# AMS_Test_Board_rev1.net
KiCad netlist of a schematic drawn in EAGLE
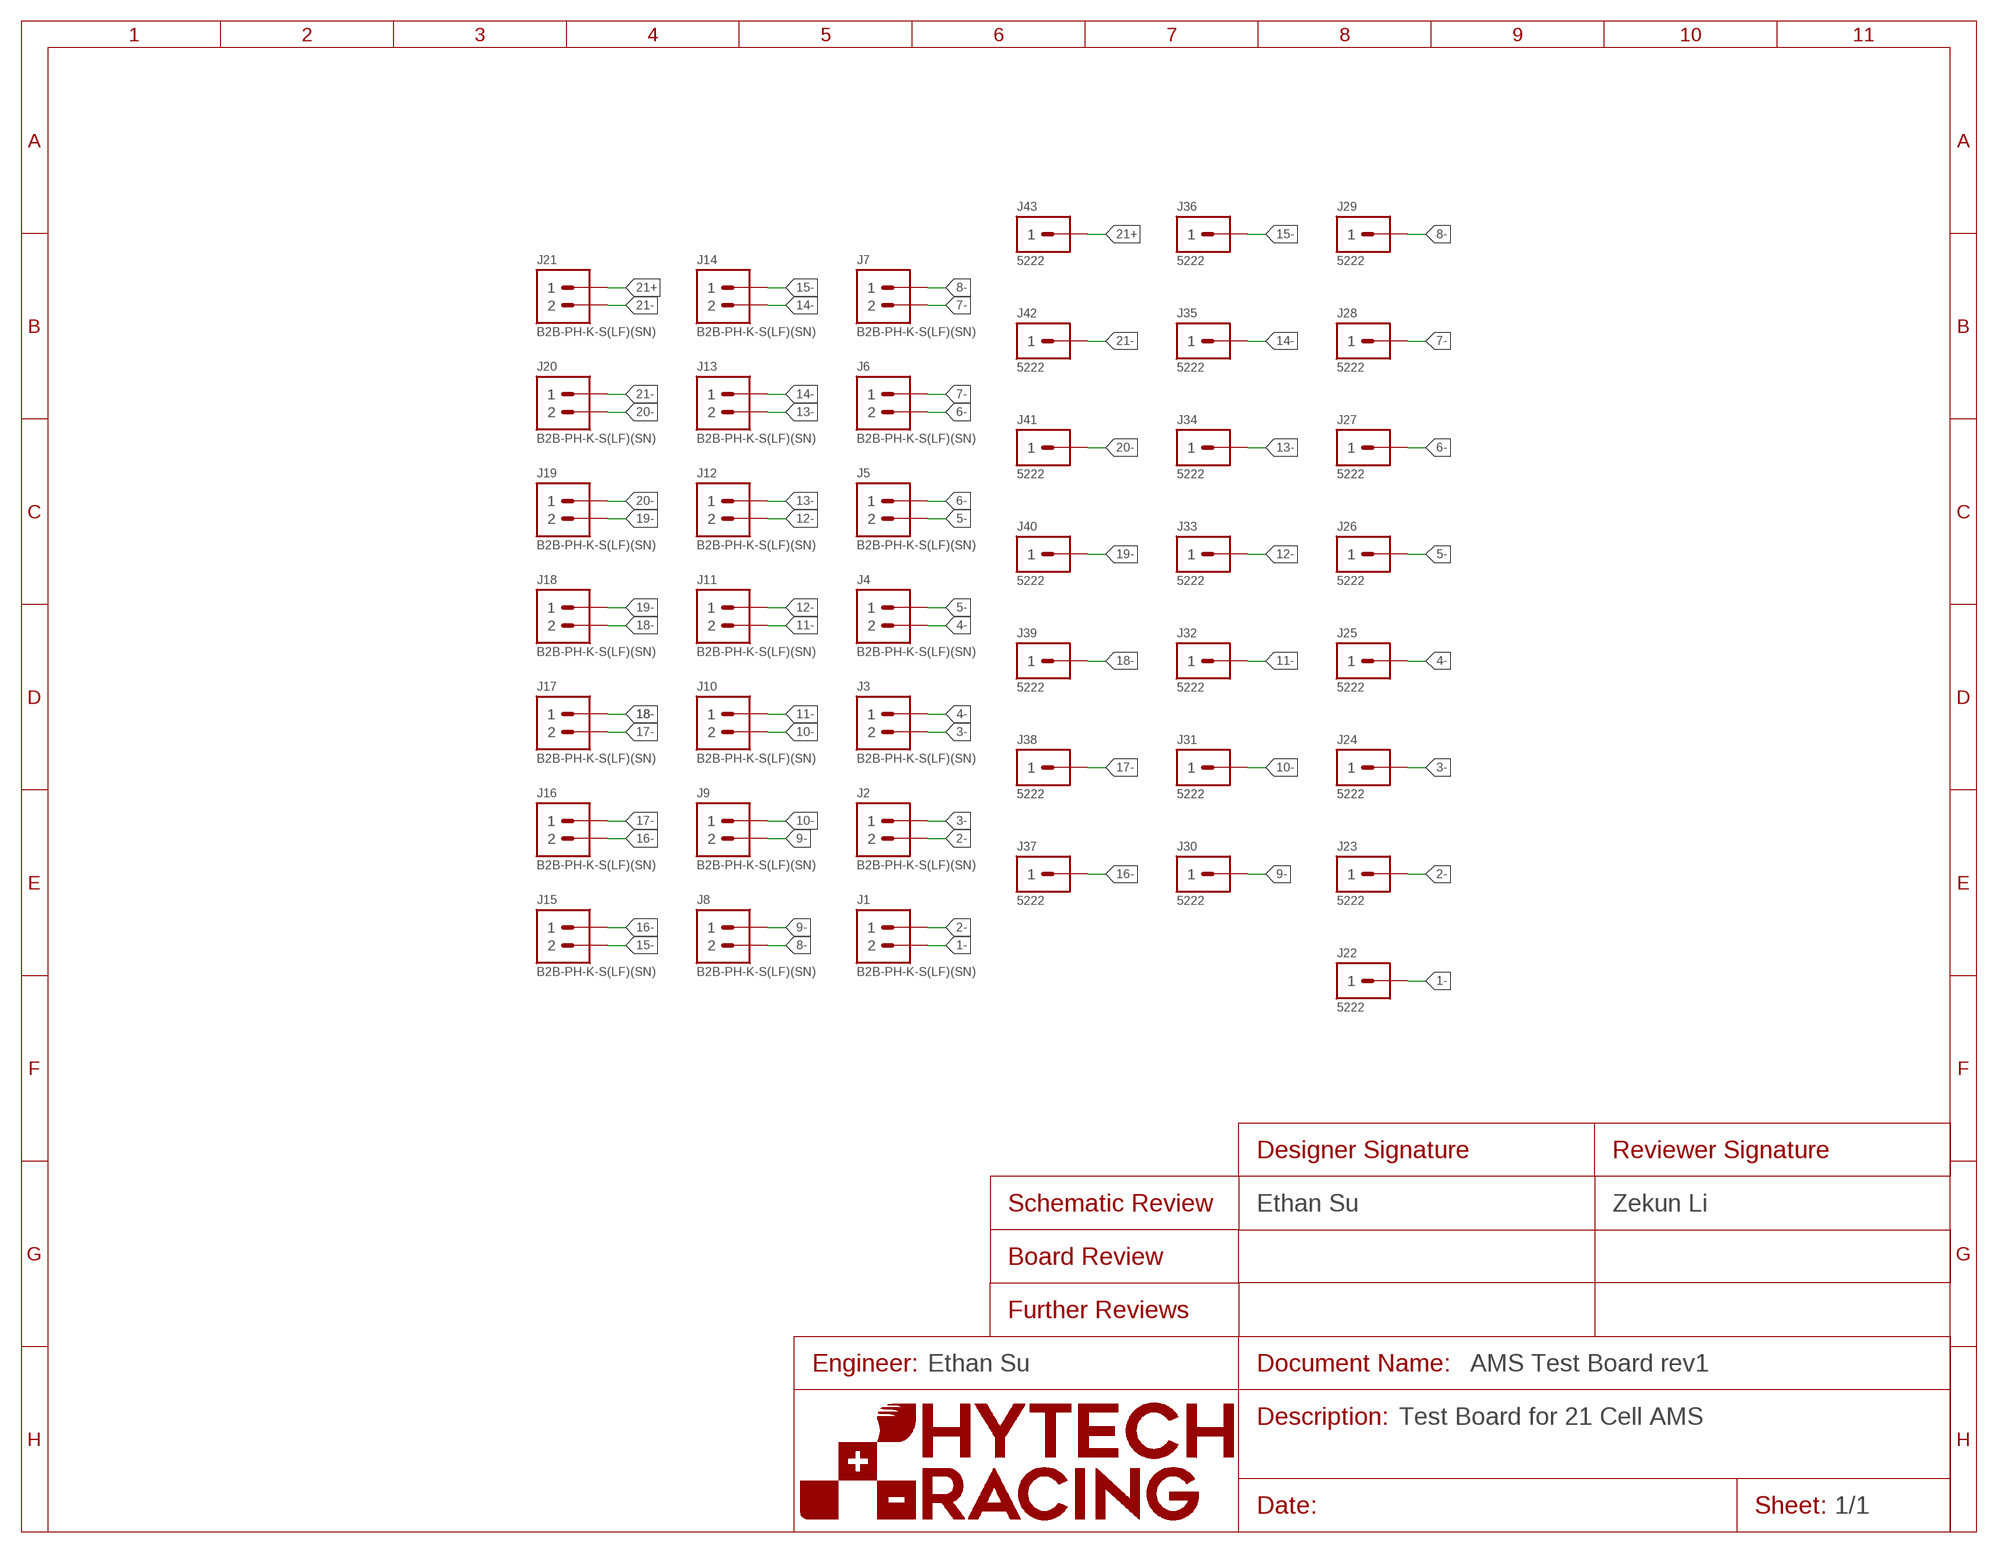
[diagram p0: schematic, sheet 1]

(export (version "E")
  (design (tool "Eeschema 10.0.6"))
  (components
    (comp (ref "J1")
      (value "CONNECTOR-2__B2B-PH-K")
      (footprint "eagle-import:B2B-PH-K")
      (fields
        (field (name "MANUFACTURER") "JST Sales America Inc.")
        (field (name "MPN") "B2B-PH-K-S(LF)(SN)")
      )
      (libsource (lib "eagle-import") (part "CONNECTOR-2_?_B2B-PH-K"))
    )
    (comp (ref "J2")
      (value "CONNECTOR-2__B2B-PH-K")
      (footprint "eagle-import:B2B-PH-K")
      (fields
        (field (name "MANUFACTURER") "JST Sales America Inc.")
        (field (name "MPN") "B2B-PH-K-S(LF)(SN)")
      )
      (libsource (lib "eagle-import") (part "CONNECTOR-2_?_B2B-PH-K"))
    )
    (comp (ref "J3")
      (value "CONNECTOR-2__B2B-PH-K")
      (footprint "eagle-import:B2B-PH-K")
      (fields
        (field (name "MANUFACTURER") "JST Sales America Inc.")
        (field (name "MPN") "B2B-PH-K-S(LF)(SN)")
      )
      (libsource (lib "eagle-import") (part "CONNECTOR-2_?_B2B-PH-K"))
    )
    (comp (ref "J4")
      (value "CONNECTOR-2__B2B-PH-K")
      (footprint "eagle-import:B2B-PH-K")
      (fields
        (field (name "MANUFACTURER") "JST Sales America Inc.")
        (field (name "MPN") "B2B-PH-K-S(LF)(SN)")
      )
      (libsource (lib "eagle-import") (part "CONNECTOR-2_?_B2B-PH-K"))
    )
    (comp (ref "J5")
      (value "CONNECTOR-2__B2B-PH-K")
      (footprint "eagle-import:B2B-PH-K")
      (fields
        (field (name "MANUFACTURER") "JST Sales America Inc.")
        (field (name "MPN") "B2B-PH-K-S(LF)(SN)")
      )
      (libsource (lib "eagle-import") (part "CONNECTOR-2_?_B2B-PH-K"))
    )
    (comp (ref "J6")
      (value "CONNECTOR-2__B2B-PH-K")
      (footprint "eagle-import:B2B-PH-K")
      (fields
        (field (name "MANUFACTURER") "JST Sales America Inc.")
        (field (name "MPN") "B2B-PH-K-S(LF)(SN)")
      )
      (libsource (lib "eagle-import") (part "CONNECTOR-2_?_B2B-PH-K"))
    )
    (comp (ref "J7")
      (value "CONNECTOR-2__B2B-PH-K")
      (footprint "eagle-import:B2B-PH-K")
      (fields
        (field (name "MANUFACTURER") "JST Sales America Inc.")
        (field (name "MPN") "B2B-PH-K-S(LF)(SN)")
      )
      (libsource (lib "eagle-import") (part "CONNECTOR-2_?_B2B-PH-K"))
    )
    (comp (ref "J8")
      (value "CONNECTOR-2__B2B-PH-K")
      (footprint "eagle-import:B2B-PH-K")
      (fields
        (field (name "MANUFACTURER") "JST Sales America Inc.")
        (field (name "MPN") "B2B-PH-K-S(LF)(SN)")
      )
      (libsource (lib "eagle-import") (part "CONNECTOR-2_?_B2B-PH-K"))
    )
    (comp (ref "J9")
      (value "CONNECTOR-2__B2B-PH-K")
      (footprint "eagle-import:B2B-PH-K")
      (fields
        (field (name "MANUFACTURER") "JST Sales America Inc.")
        (field (name "MPN") "B2B-PH-K-S(LF)(SN)")
      )
      (libsource (lib "eagle-import") (part "CONNECTOR-2_?_B2B-PH-K"))
    )
    (comp (ref "J10")
      (value "CONNECTOR-2__B2B-PH-K")
      (footprint "eagle-import:B2B-PH-K")
      (fields
        (field (name "MANUFACTURER") "JST Sales America Inc.")
        (field (name "MPN") "B2B-PH-K-S(LF)(SN)")
      )
      (libsource (lib "eagle-import") (part "CONNECTOR-2_?_B2B-PH-K"))
    )
    (comp (ref "J11")
      (value "CONNECTOR-2__B2B-PH-K")
      (footprint "eagle-import:B2B-PH-K")
      (fields
        (field (name "MANUFACTURER") "JST Sales America Inc.")
        (field (name "MPN") "B2B-PH-K-S(LF)(SN)")
      )
      (libsource (lib "eagle-import") (part "CONNECTOR-2_?_B2B-PH-K"))
    )
    (comp (ref "J12")
      (value "CONNECTOR-2__B2B-PH-K")
      (footprint "eagle-import:B2B-PH-K")
      (fields
        (field (name "MANUFACTURER") "JST Sales America Inc.")
        (field (name "MPN") "B2B-PH-K-S(LF)(SN)")
      )
      (libsource (lib "eagle-import") (part "CONNECTOR-2_?_B2B-PH-K"))
    )
    (comp (ref "J13")
      (value "CONNECTOR-2__B2B-PH-K")
      (footprint "eagle-import:B2B-PH-K")
      (fields
        (field (name "MANUFACTURER") "JST Sales America Inc.")
        (field (name "MPN") "B2B-PH-K-S(LF)(SN)")
      )
      (libsource (lib "eagle-import") (part "CONNECTOR-2_?_B2B-PH-K"))
    )
    (comp (ref "J14")
      (value "CONNECTOR-2__B2B-PH-K")
      (footprint "eagle-import:B2B-PH-K")
      (fields
        (field (name "MANUFACTURER") "JST Sales America Inc.")
        (field (name "MPN") "B2B-PH-K-S(LF)(SN)")
      )
      (libsource (lib "eagle-import") (part "CONNECTOR-2_?_B2B-PH-K"))
    )
    (comp (ref "J15")
      (value "CONNECTOR-2__B2B-PH-K")
      (footprint "eagle-import:B2B-PH-K")
      (fields
        (field (name "MANUFACTURER") "JST Sales America Inc.")
        (field (name "MPN") "B2B-PH-K-S(LF)(SN)")
      )
      (libsource (lib "eagle-import") (part "CONNECTOR-2_?_B2B-PH-K"))
    )
    (comp (ref "J16")
      (value "CONNECTOR-2__B2B-PH-K")
      (footprint "eagle-import:B2B-PH-K")
      (fields
        (field (name "MANUFACTURER") "JST Sales America Inc.")
        (field (name "MPN") "B2B-PH-K-S(LF)(SN)")
      )
      (libsource (lib "eagle-import") (part "CONNECTOR-2_?_B2B-PH-K"))
    )
    (comp (ref "J17")
      (value "CONNECTOR-2__B2B-PH-K")
      (footprint "eagle-import:B2B-PH-K")
      (fields
        (field (name "MANUFACTURER") "JST Sales America Inc.")
        (field (name "MPN") "B2B-PH-K-S(LF)(SN)")
      )
      (libsource (lib "eagle-import") (part "CONNECTOR-2_?_B2B-PH-K"))
    )
    (comp (ref "J18")
      (value "CONNECTOR-2__B2B-PH-K")
      (footprint "eagle-import:B2B-PH-K")
      (fields
        (field (name "MANUFACTURER") "JST Sales America Inc.")
        (field (name "MPN") "B2B-PH-K-S(LF)(SN)")
      )
      (libsource (lib "eagle-import") (part "CONNECTOR-2_?_B2B-PH-K"))
    )
    (comp (ref "J19")
      (value "CONNECTOR-2__B2B-PH-K")
      (footprint "eagle-import:B2B-PH-K")
      (fields
        (field (name "MANUFACTURER") "JST Sales America Inc.")
        (field (name "MPN") "B2B-PH-K-S(LF)(SN)")
      )
      (libsource (lib "eagle-import") (part "CONNECTOR-2_?_B2B-PH-K"))
    )
    (comp (ref "J20")
      (value "CONNECTOR-2__B2B-PH-K")
      (footprint "eagle-import:B2B-PH-K")
      (fields
        (field (name "MANUFACTURER") "JST Sales America Inc.")
        (field (name "MPN") "B2B-PH-K-S(LF)(SN)")
      )
      (libsource (lib "eagle-import") (part "CONNECTOR-2_?_B2B-PH-K"))
    )
    (comp (ref "J21")
      (value "CONNECTOR-2__B2B-PH-K")
      (footprint "eagle-import:B2B-PH-K")
      (fields
        (field (name "MANUFACTURER") "JST Sales America Inc.")
        (field (name "MPN") "B2B-PH-K-S(LF)(SN)")
      )
      (libsource (lib "eagle-import") (part "CONNECTOR-2_?_B2B-PH-K"))
    )
    (comp (ref "J22")
      (value "CONNECTOR-1_5222")
      (footprint "eagle-import:5222")
      (fields (field (name "MPN") "5222") (field (name "MANUFACTURER") "Keystone Electronics"))
      (libsource (lib "eagle-import") (part "CONNECTOR-1_?5222"))
    )
    (comp (ref "J23")
      (value "CONNECTOR-1_5222")
      (footprint "eagle-import:5222")
      (fields (field (name "MPN") "5222") (field (name "MANUFACTURER") "Keystone Electronics"))
      (libsource (lib "eagle-import") (part "CONNECTOR-1_?5222"))
    )
    (comp (ref "J24")
      (value "CONNECTOR-1_5222")
      (footprint "eagle-import:5222")
      (fields (field (name "MPN") "5222") (field (name "MANUFACTURER") "Keystone Electronics"))
      (libsource (lib "eagle-import") (part "CONNECTOR-1_?5222"))
    )
    (comp (ref "J25")
      (value "CONNECTOR-1_5222")
      (footprint "eagle-import:5222")
      (fields (field (name "MPN") "5222") (field (name "MANUFACTURER") "Keystone Electronics"))
      (libsource (lib "eagle-import") (part "CONNECTOR-1_?5222"))
    )
    (comp (ref "J26")
      (value "CONNECTOR-1_5222")
      (footprint "eagle-import:5222")
      (fields (field (name "MPN") "5222") (field (name "MANUFACTURER") "Keystone Electronics"))
      (libsource (lib "eagle-import") (part "CONNECTOR-1_?5222"))
    )
    (comp (ref "J27")
      (value "CONNECTOR-1_5222")
      (footprint "eagle-import:5222")
      (fields (field (name "MPN") "5222") (field (name "MANUFACTURER") "Keystone Electronics"))
      (libsource (lib "eagle-import") (part "CONNECTOR-1_?5222"))
    )
    (comp (ref "J28")
      (value "CONNECTOR-1_5222")
      (footprint "eagle-import:5222")
      (fields (field (name "MPN") "5222") (field (name "MANUFACTURER") "Keystone Electronics"))
      (libsource (lib "eagle-import") (part "CONNECTOR-1_?5222"))
    )
    (comp (ref "J29")
      (value "CONNECTOR-1_5222")
      (footprint "eagle-import:5222")
      (fields (field (name "MPN") "5222") (field (name "MANUFACTURER") "Keystone Electronics"))
      (libsource (lib "eagle-import") (part "CONNECTOR-1_?5222"))
    )
    (comp (ref "J30")
      (value "CONNECTOR-1_5222")
      (footprint "eagle-import:5222")
      (fields (field (name "MPN") "5222") (field (name "MANUFACTURER") "Keystone Electronics"))
      (libsource (lib "eagle-import") (part "CONNECTOR-1_?5222"))
    )
    (comp (ref "J31")
      (value "CONNECTOR-1_5222")
      (footprint "eagle-import:5222")
      (fields (field (name "MPN") "5222") (field (name "MANUFACTURER") "Keystone Electronics"))
      (libsource (lib "eagle-import") (part "CONNECTOR-1_?5222"))
    )
    (comp (ref "J32")
      (value "CONNECTOR-1_5222")
      (footprint "eagle-import:5222")
      (fields (field (name "MPN") "5222") (field (name "MANUFACTURER") "Keystone Electronics"))
      (libsource (lib "eagle-import") (part "CONNECTOR-1_?5222"))
    )
    (comp (ref "J33")
      (value "CONNECTOR-1_5222")
      (footprint "eagle-import:5222")
      (fields (field (name "MPN") "5222") (field (name "MANUFACTURER") "Keystone Electronics"))
      (libsource (lib "eagle-import") (part "CONNECTOR-1_?5222"))
    )
    (comp (ref "J34")
      (value "CONNECTOR-1_5222")
      (footprint "eagle-import:5222")
      (fields (field (name "MPN") "5222") (field (name "MANUFACTURER") "Keystone Electronics"))
      (libsource (lib "eagle-import") (part "CONNECTOR-1_?5222"))
    )
    (comp (ref "J35")
      (value "CONNECTOR-1_5222")
      (footprint "eagle-import:5222")
      (fields (field (name "MPN") "5222") (field (name "MANUFACTURER") "Keystone Electronics"))
      (libsource (lib "eagle-import") (part "CONNECTOR-1_?5222"))
    )
    (comp (ref "J36")
      (value "CONNECTOR-1_5222")
      (footprint "eagle-import:5222")
      (fields (field (name "MPN") "5222") (field (name "MANUFACTURER") "Keystone Electronics"))
      (libsource (lib "eagle-import") (part "CONNECTOR-1_?5222"))
    )
    (comp (ref "J37")
      (value "CONNECTOR-1_5222")
      (footprint "eagle-import:5222")
      (fields (field (name "MPN") "5222") (field (name "MANUFACTURER") "Keystone Electronics"))
      (libsource (lib "eagle-import") (part "CONNECTOR-1_?5222"))
    )
    (comp (ref "J38")
      (value "CONNECTOR-1_5222")
      (footprint "eagle-import:5222")
      (fields (field (name "MPN") "5222") (field (name "MANUFACTURER") "Keystone Electronics"))
      (libsource (lib "eagle-import") (part "CONNECTOR-1_?5222"))
    )
    (comp (ref "J39")
      (value "CONNECTOR-1_5222")
      (footprint "eagle-import:5222")
      (fields (field (name "MPN") "5222") (field (name "MANUFACTURER") "Keystone Electronics"))
      (libsource (lib "eagle-import") (part "CONNECTOR-1_?5222"))
    )
    (comp (ref "J40")
      (value "CONNECTOR-1_5222")
      (footprint "eagle-import:5222")
      (fields (field (name "MPN") "5222") (field (name "MANUFACTURER") "Keystone Electronics"))
      (libsource (lib "eagle-import") (part "CONNECTOR-1_?5222"))
    )
    (comp (ref "J41")
      (value "CONNECTOR-1_5222")
      (footprint "eagle-import:5222")
      (fields (field (name "MPN") "5222") (field (name "MANUFACTURER") "Keystone Electronics"))
      (libsource (lib "eagle-import") (part "CONNECTOR-1_?5222"))
    )
    (comp (ref "J42")
      (value "CONNECTOR-1_5222")
      (footprint "eagle-import:5222")
      (fields (field (name "MPN") "5222") (field (name "MANUFACTURER") "Keystone Electronics"))
      (libsource (lib "eagle-import") (part "CONNECTOR-1_?5222"))
    )
    (comp (ref "J43")
      (value "CONNECTOR-1_5222")
      (footprint "eagle-import:5222")
      (fields (field (name "MPN") "5222") (field (name "MANUFACTURER") "Keystone Electronics"))
      (libsource (lib "eagle-import") (part "CONNECTOR-1_?5222"))
    )
  )
  (nets
    (net (code "1") (name "1-") (class "Default")
      (node (ref "J1") (pin "2") (pinfunction "2_2") (pintype "passive"))
      (node (ref "J22") (pin "1") (pinfunction "1_1") (pintype "passive"))
    )
    (net (code "2") (name "2-") (class "Default")
      (node (ref "J1") (pin "1") (pinfunction "1_1") (pintype "passive"))
      (node (ref "J2") (pin "2") (pinfunction "2_2") (pintype "passive"))
      (node (ref "J23") (pin "1") (pinfunction "1_1") (pintype "passive"))
    )
    (net (code "3") (name "3-") (class "Default")
      (node (ref "J2") (pin "1") (pinfunction "1_1") (pintype "passive"))
      (node (ref "J24") (pin "1") (pinfunction "1_1") (pintype "passive"))
      (node (ref "J3") (pin "2") (pinfunction "2_2") (pintype "passive"))
    )
    (net (code "4") (name "4-") (class "Default")
      (node (ref "J25") (pin "1") (pinfunction "1_1") (pintype "passive"))
      (node (ref "J3") (pin "1") (pinfunction "1_1") (pintype "passive"))
      (node (ref "J4") (pin "2") (pinfunction "2_2") (pintype "passive"))
    )
    (net (code "5") (name "5-") (class "Default")
      (node (ref "J26") (pin "1") (pinfunction "1_1") (pintype "passive"))
      (node (ref "J4") (pin "1") (pinfunction "1_1") (pintype "passive"))
      (node (ref "J5") (pin "2") (pinfunction "2_2") (pintype "passive"))
    )
    (net (code "6") (name "6-") (class "Default")
      (node (ref "J27") (pin "1") (pinfunction "1_1") (pintype "passive"))
      (node (ref "J5") (pin "1") (pinfunction "1_1") (pintype "passive"))
      (node (ref "J6") (pin "2") (pinfunction "2_2") (pintype "passive"))
    )
    (net (code "7") (name "7-") (class "Default")
      (node (ref "J28") (pin "1") (pinfunction "1_1") (pintype "passive"))
      (node (ref "J6") (pin "1") (pinfunction "1_1") (pintype "passive"))
      (node (ref "J7") (pin "2") (pinfunction "2_2") (pintype "passive"))
    )
    (net (code "8") (name "8-") (class "Default")
      (node (ref "J29") (pin "1") (pinfunction "1_1") (pintype "passive"))
      (node (ref "J7") (pin "1") (pinfunction "1_1") (pintype "passive"))
      (node (ref "J8") (pin "2") (pinfunction "2_2") (pintype "passive"))
    )
    (net (code "9") (name "9-") (class "Default")
      (node (ref "J30") (pin "1") (pinfunction "1_1") (pintype "passive"))
      (node (ref "J8") (pin "1") (pinfunction "1_1") (pintype "passive"))
      (node (ref "J9") (pin "2") (pinfunction "2_2") (pintype "passive"))
    )
    (net (code "10") (name "10-") (class "Default")
      (node (ref "J10") (pin "2") (pinfunction "2_2") (pintype "passive"))
      (node (ref "J31") (pin "1") (pinfunction "1_1") (pintype "passive"))
      (node (ref "J9") (pin "1") (pinfunction "1_1") (pintype "passive"))
    )
    (net (code "11") (name "11-") (class "Default")
      (node (ref "J10") (pin "1") (pinfunction "1_1") (pintype "passive"))
      (node (ref "J11") (pin "2") (pinfunction "2_2") (pintype "passive"))
      (node (ref "J32") (pin "1") (pinfunction "1_1") (pintype "passive"))
    )
    (net (code "12") (name "12-") (class "Default")
      (node (ref "J11") (pin "1") (pinfunction "1_1") (pintype "passive"))
      (node (ref "J12") (pin "2") (pinfunction "2_2") (pintype "passive"))
      (node (ref "J33") (pin "1") (pinfunction "1_1") (pintype "passive"))
    )
    (net (code "13") (name "13-") (class "Default")
      (node (ref "J12") (pin "1") (pinfunction "1_1") (pintype "passive"))
      (node (ref "J13") (pin "2") (pinfunction "2_2") (pintype "passive"))
      (node (ref "J34") (pin "1") (pinfunction "1_1") (pintype "passive"))
    )
    (net (code "14") (name "14-") (class "Default")
      (node (ref "J13") (pin "1") (pinfunction "1_1") (pintype "passive"))
      (node (ref "J14") (pin "2") (pinfunction "2_2") (pintype "passive"))
      (node (ref "J35") (pin "1") (pinfunction "1_1") (pintype "passive"))
    )
    (net (code "15") (name "15-") (class "Default")
      (node (ref "J14") (pin "1") (pinfunction "1_1") (pintype "passive"))
      (node (ref "J15") (pin "2") (pinfunction "2_2") (pintype "passive"))
      (node (ref "J36") (pin "1") (pinfunction "1_1") (pintype "passive"))
    )
    (net (code "16") (name "16-") (class "Default")
      (node (ref "J15") (pin "1") (pinfunction "1_1") (pintype "passive"))
      (node (ref "J16") (pin "2") (pinfunction "2_2") (pintype "passive"))
      (node (ref "J37") (pin "1") (pinfunction "1_1") (pintype "passive"))
    )
    (net (code "17") (name "17-") (class "Default")
      (node (ref "J16") (pin "1") (pinfunction "1_1") (pintype "passive"))
      (node (ref "J17") (pin "2") (pinfunction "2_2") (pintype "passive"))
      (node (ref "J38") (pin "1") (pinfunction "1_1") (pintype "passive"))
    )
    (net (code "18") (name "18-") (class "Default")
      (node (ref "J17") (pin "1") (pinfunction "1_1") (pintype "passive"))
      (node (ref "J18") (pin "2") (pinfunction "2_2") (pintype "passive"))
      (node (ref "J39") (pin "1") (pinfunction "1_1") (pintype "passive"))
    )
    (net (code "19") (name "19-") (class "Default")
      (node (ref "J18") (pin "1") (pinfunction "1_1") (pintype "passive"))
      (node (ref "J19") (pin "2") (pinfunction "2_2") (pintype "passive"))
      (node (ref "J40") (pin "1") (pinfunction "1_1") (pintype "passive"))
    )
    (net (code "20") (name "20-") (class "Default")
      (node (ref "J19") (pin "1") (pinfunction "1_1") (pintype "passive"))
      (node (ref "J20") (pin "2") (pinfunction "2_2") (pintype "passive"))
      (node (ref "J41") (pin "1") (pinfunction "1_1") (pintype "passive"))
    )
    (net (code "21") (name "21+") (class "Default")
      (node (ref "J21") (pin "1") (pinfunction "1_1") (pintype "passive"))
      (node (ref "J43") (pin "1") (pinfunction "1_1") (pintype "passive"))
    )
    (net (code "22") (name "21-") (class "Default")
      (node (ref "J20") (pin "1") (pinfunction "1_1") (pintype "passive"))
      (node (ref "J21") (pin "2") (pinfunction "2_2") (pintype "passive"))
      (node (ref "J42") (pin "1") (pinfunction "1_1") (pintype "passive"))
    )
  )
)
